# Camera-Connectors.net
KiCad netlist of a schematic drawn in Altium Designer
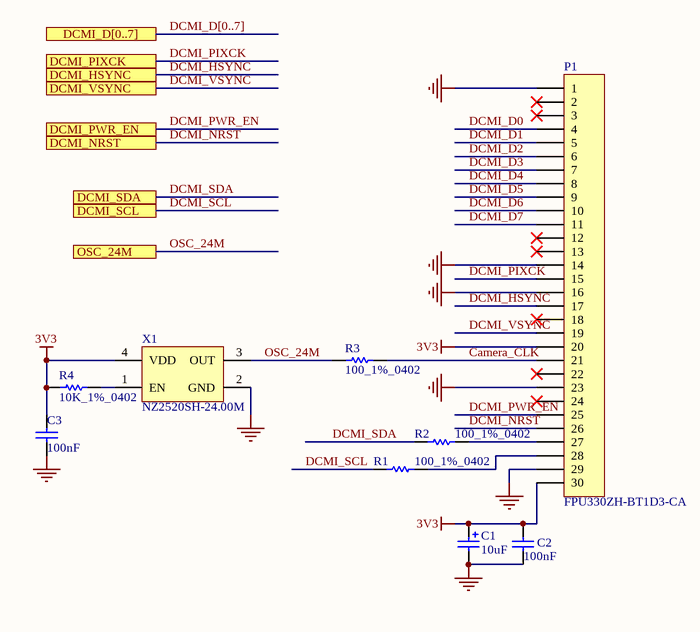
[diagram p0: Camera-Connectors.SchDoc]

(export (version "E")
  (design (tool "Eeschema 10.0.6"))
  (components
    (comp (ref "C1")
      (value "10uF")
      (footprint "TAN-A")
      (description "Polarized Capacitor,10uF,10V,10%,typeA,VISHAY")
      (libsource (lib "MCD_TOOLS") (part "Cap_10uF_POL_10%_TANA"))
    )
    (comp (ref "C2")
      (value "100nF")
      (footprint "0402C")
      (description "Capacitor,100nF,16V,X7R,10%,0402,YAGEO")
      (libsource (lib "MCD_TOOLS") (part "Cap_100nF_X7R_10%_0402"))
    )
    (comp (ref "C3")
      (value "100nF")
      (footprint "0402C")
      (description "Capacitor,100nF,16V,X7R,10%,0402,YAGEO")
      (libsource (lib "MCD_TOOLS") (part "Cap_100nF_X7R_10%_0402"))
    )
    (comp (ref "P1")
      (value "FPU330ZH-BT1D3-CA")
      (footprint "FPU330ZH-BT1D3-CA")
      (description "TOWNES -  Connector FFC/FPC ZIF 0.5mm 30 pins, Lower Contacts")
      (libsource (lib "MCD_TOOLS") (part "FPU330ZH-BT1D3-CA"))
    )
    (comp (ref "R1")
      (value "100_1%_0402")
      (footprint "0402R")
      (description "Resistor,100,0402,1%,YAGEO")
      (libsource (lib "MCD_TOOLS") (part "Res_100_1%_0402"))
    )
    (comp (ref "R2")
      (value "100_1%_0402")
      (footprint "0402R")
      (description "Resistor,100,0402,1%,YAGEO")
      (libsource (lib "MCD_TOOLS") (part "Res_100_1%_0402"))
    )
    (comp (ref "R3")
      (value "100_1%_0402")
      (footprint "0402R")
      (description "Resistor,100,0402,1%,YAGEO")
      (libsource (lib "MCD_TOOLS") (part "Res_100_1%_0402"))
    )
    (comp (ref "R4")
      (value "10K_1%_0402")
      (footprint "0402R")
      (description "Resistor,10K,0402,1%,YAGEO")
      (libsource (lib "MCD_TOOLS") (part "Res_10K_1%_0402"))
    )
    (comp (ref "X1")
      (value "NZ2520SH-24.00M")
      (footprint "NZ2520SH_4P")
      (description "Oscillator 24.00Mhz, -+50PPM, 3.3V, Temp -55 to +125°C")
      (libsource (lib "MCD_TOOLS") (part "OSC_24M_NZ2520SB"))
    )
  )
  (nets
    (net (code "1") (name "/Camera_CLK") (class "Default")
      (node (ref "P1") (pin "21") (pinfunction "21_21") (pintype "passive"))
      (node (ref "R3") (pin "2") (pinfunction "2_2") (pintype "passive"))
    )
    (net (code "2") (name "/DCMI_D0") (class "Default")
      (node (ref "P1") (pin "4") (pinfunction "4_4") (pintype "passive"))
    )
    (net (code "3") (name "/DCMI_D1") (class "Default")
      (node (ref "P1") (pin "5") (pinfunction "5_5") (pintype "passive"))
    )
    (net (code "4") (name "/DCMI_D2") (class "Default")
      (node (ref "P1") (pin "6") (pinfunction "6_6") (pintype "passive"))
    )
    (net (code "5") (name "/DCMI_D3") (class "Default")
      (node (ref "P1") (pin "7") (pinfunction "7_7") (pintype "passive"))
    )
    (net (code "6") (name "/DCMI_D4") (class "Default")
      (node (ref "P1") (pin "8") (pinfunction "8_8") (pintype "passive"))
    )
    (net (code "7") (name "/DCMI_D5") (class "Default")
      (node (ref "P1") (pin "9") (pinfunction "9_9") (pintype "passive"))
    )
    (net (code "8") (name "/DCMI_D6") (class "Default")
      (node (ref "P1") (pin "10") (pinfunction "10_10") (pintype "passive"))
    )
    (net (code "9") (name "/DCMI_D7") (class "Default")
      (node (ref "P1") (pin "11") (pinfunction "11_11") (pintype "passive"))
    )
    (net (code "11") (name "/DCMI_HSYNC") (class "Default")
      (node (ref "P1") (pin "17") (pinfunction "17_17") (pintype "passive"))
    )
    (net (code "12") (name "/DCMI_NRST") (class "Default")
      (node (ref "P1") (pin "26") (pinfunction "26_26") (pintype "passive"))
    )
    (net (code "13") (name "/DCMI_PIXCK") (class "Default")
      (node (ref "P1") (pin "15") (pinfunction "15_15") (pintype "passive"))
    )
    (net (code "14") (name "/DCMI_PWR_EN") (class "Default")
      (node (ref "P1") (pin "25") (pinfunction "25_25") (pintype "passive"))
    )
    (net (code "15") (name "/DCMI_SCL") (class "Default")
      (node (ref "R1") (pin "1") (pinfunction "1_1") (pintype "passive"))
    )
    (net (code "16") (name "/DCMI_SDA") (class "Default")
      (node (ref "R2") (pin "1") (pinfunction "1_1") (pintype "passive"))
    )
    (net (code "17") (name "/DCMI_VSYNC") (class "Default")
      (node (ref "P1") (pin "19") (pinfunction "19_19") (pintype "passive"))
    )
    (net (code "18") (name "/OSC_24M") (class "Default")
      (node (ref "R3") (pin "1") (pinfunction "1_1") (pintype "passive"))
      (node (ref "X1") (pin "3") (pinfunction "OUT_3") (pintype "passive"))
    )
    (net (code "19") (name "3V3") (class "Default")
      (node (ref "C1") (pin "1") (pinfunction "1_1") (pintype "passive"))
      (node (ref "C2") (pin "2") (pinfunction "2_2") (pintype "passive"))
      (node (ref "C3") (pin "2") (pinfunction "2_2") (pintype "passive"))
      (node (ref "P1") (pin "20") (pinfunction "20_20") (pintype "passive"))
      (node (ref "P1") (pin "30") (pinfunction "30_30") (pintype "passive"))
      (node (ref "R4") (pin "1") (pinfunction "1_1") (pintype "passive"))
      (node (ref "X1") (pin "4") (pinfunction "VDD_4") (pintype "passive"))
    )
    (net (code "20") (name "GND") (class "Default")
      (node (ref "C1") (pin "2") (pinfunction "2_2") (pintype "passive"))
      (node (ref "C2") (pin "1") (pinfunction "1_1") (pintype "passive"))
      (node (ref "C3") (pin "1") (pinfunction "1_1") (pintype "passive"))
      (node (ref "P1") (pin "1") (pinfunction "1_1") (pintype "passive"))
      (node (ref "P1") (pin "14") (pinfunction "14_14") (pintype "passive"))
      (node (ref "P1") (pin "16") (pinfunction "16_16") (pintype "passive"))
      (node (ref "P1") (pin "23") (pinfunction "23_23") (pintype "passive"))
      (node (ref "P1") (pin "29") (pinfunction "29_29") (pintype "passive"))
      (node (ref "X1") (pin "2") (pinfunction "GND_2") (pintype "passive"))
    )
    (net (code "21") (name "Net-(P1-Pad27)") (class "Default")
      (node (ref "P1") (pin "27") (pinfunction "27_27") (pintype "passive"))
      (node (ref "R2") (pin "2") (pinfunction "2_2") (pintype "passive"))
    )
    (net (code "22") (name "Net-(P1-Pad28)") (class "Default")
      (node (ref "P1") (pin "28") (pinfunction "28_28") (pintype "passive"))
      (node (ref "R1") (pin "2") (pinfunction "2_2") (pintype "passive"))
    )
    (net (code "23") (name "Net-(X1-EN)") (class "Default")
      (node (ref "R4") (pin "2") (pinfunction "2_2") (pintype "passive"))
      (node (ref "X1") (pin "1") (pinfunction "EN_1") (pintype "passive"))
    )
    (net (code "24") (name "unconnected-(P1-Pad2)") (class "Default")
      (node (ref "P1") (pin "2") (pinfunction "2_2") (pintype "passive+no_connect"))
    )
    (net (code "25") (name "unconnected-(P1-Pad3)") (class "Default")
      (node (ref "P1") (pin "3") (pinfunction "3_3") (pintype "passive+no_connect"))
    )
    (net (code "26") (name "unconnected-(P1-Pad12)") (class "Default")
      (node (ref "P1") (pin "12") (pinfunction "12_12") (pintype "passive+no_connect"))
    )
    (net (code "27") (name "unconnected-(P1-Pad13)") (class "Default")
      (node (ref "P1") (pin "13") (pinfunction "13_13") (pintype "passive+no_connect"))
    )
    (net (code "28") (name "unconnected-(P1-Pad18)") (class "Default")
      (node (ref "P1") (pin "18") (pinfunction "18_18") (pintype "passive+no_connect"))
    )
    (net (code "29") (name "unconnected-(P1-Pad22)") (class "Default")
      (node (ref "P1") (pin "22") (pinfunction "22_22") (pintype "passive+no_connect"))
    )
    (net (code "30") (name "unconnected-(P1-Pad24)") (class "Default")
      (node (ref "P1") (pin "24") (pinfunction "24_24") (pintype "passive+no_connect"))
    )
  )
)
